# First_Board.net
KiCad netlist of a schematic drawn in EAGLE
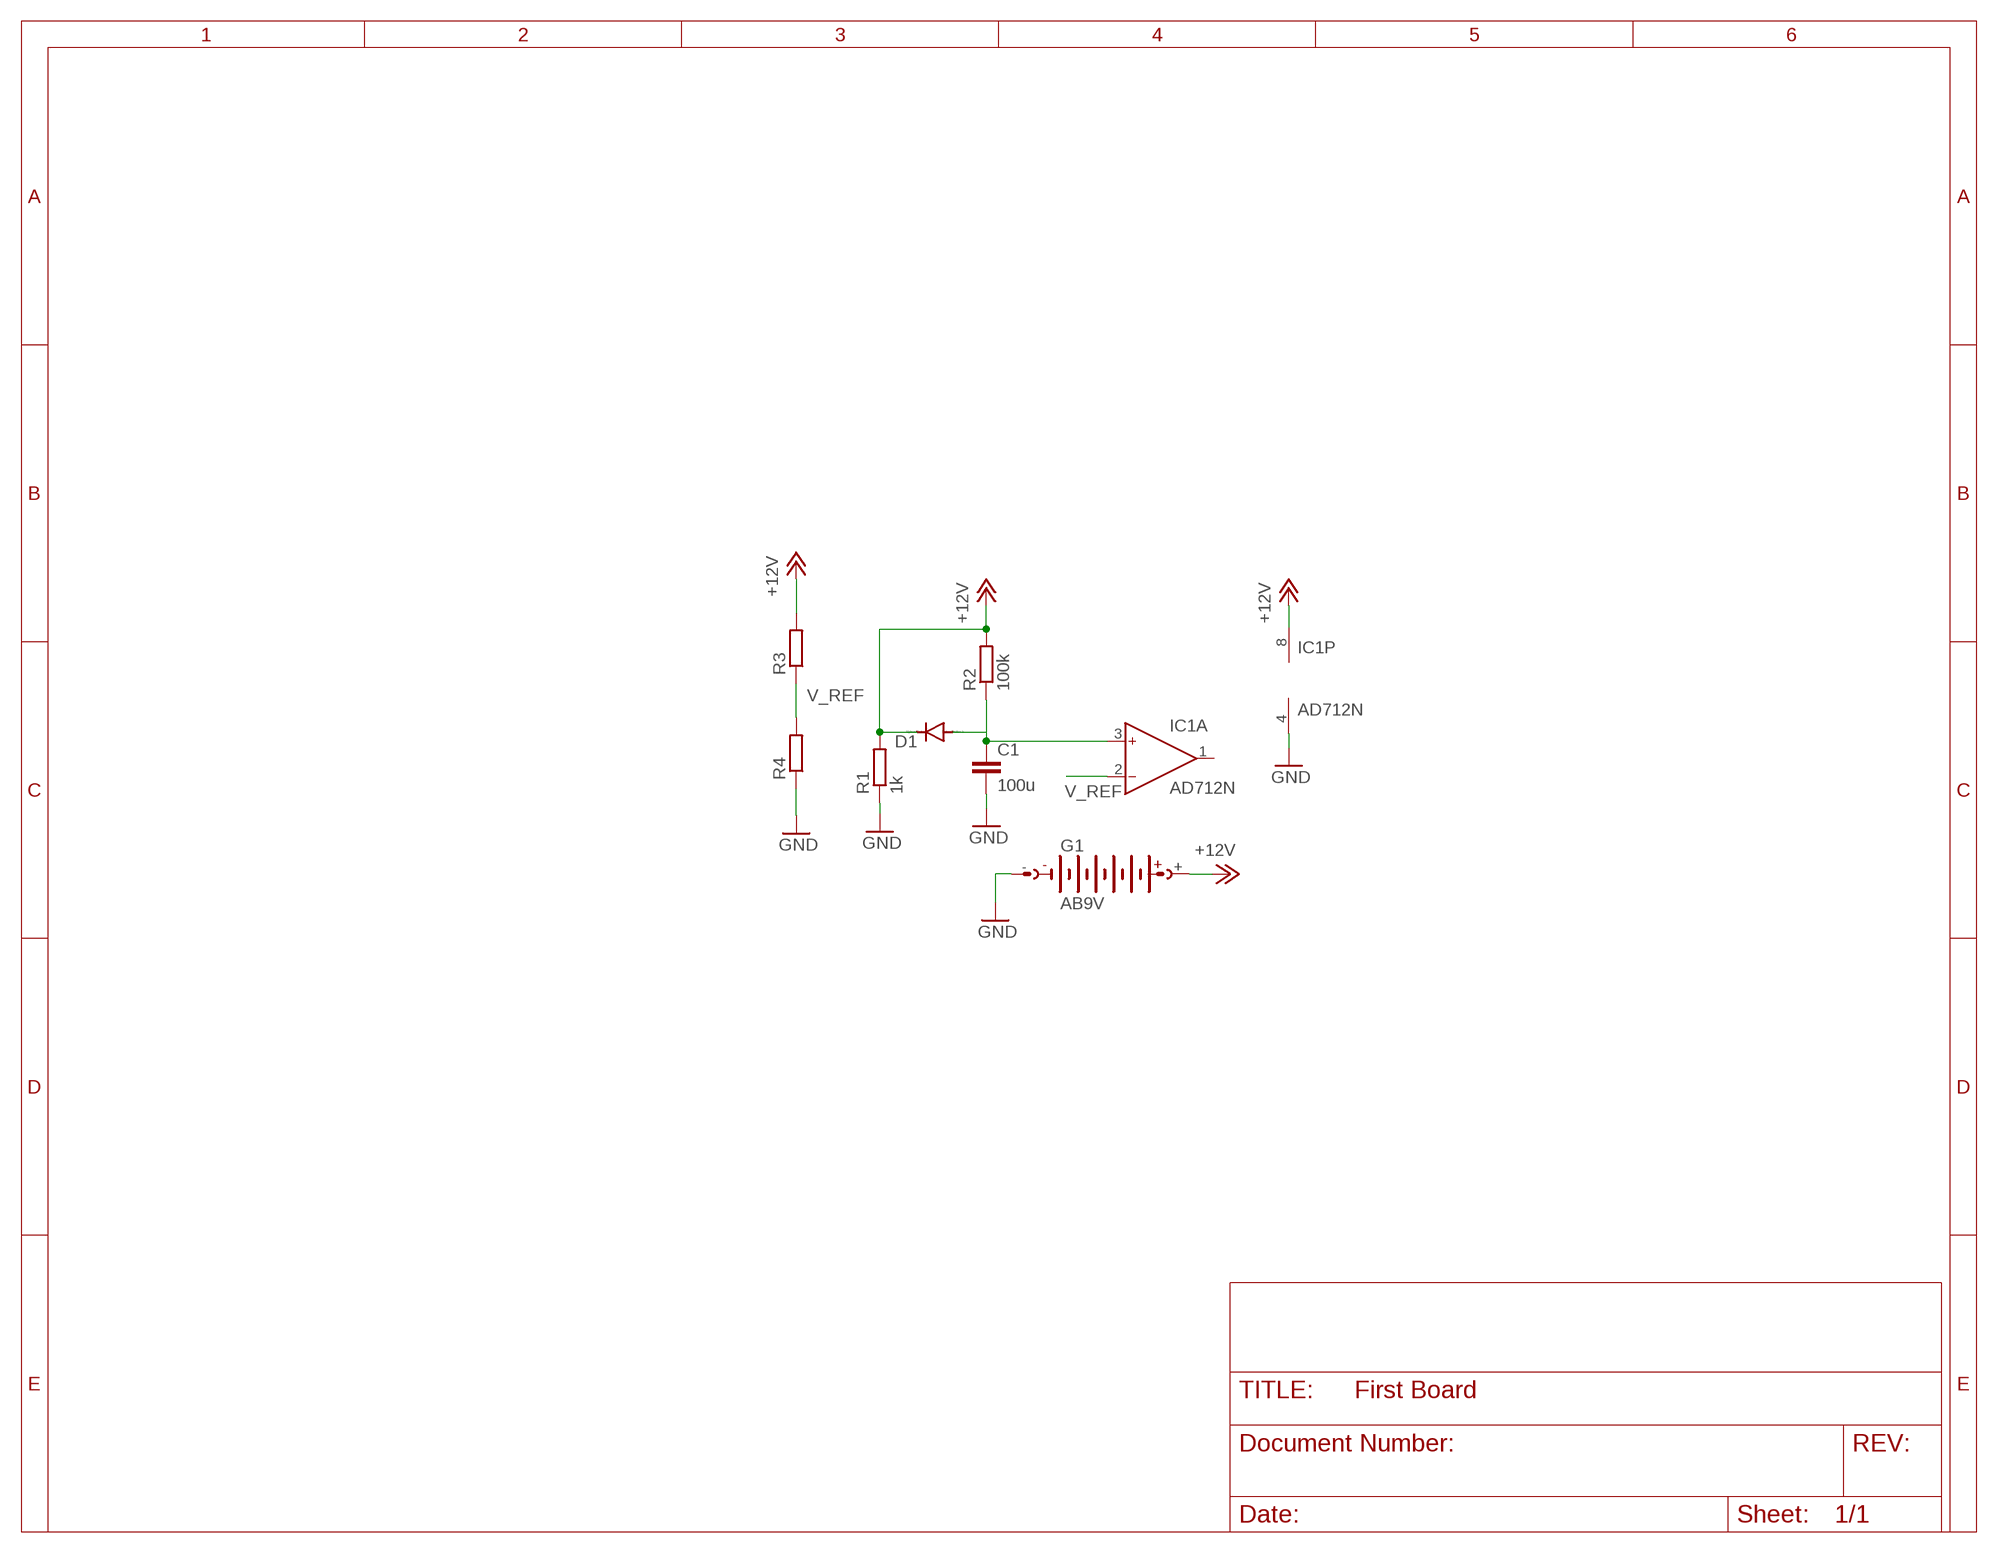
[diagram p0: schematic, sheet 1]

(export (version "E")
  (design (tool "Eeschema 10.0.6"))
  (components
    (comp (ref "C1")
      (value "100u")
      (footprint "eagle-import:C0805")
      (libsource (lib "eagle-import") (part "C-EUC0805"))
    )
    (comp (ref "D1")
      (value "DIODE-DO214AC")
      (footprint "eagle-import:DO214AC")
      (libsource (lib "eagle-import") (part "DIODE-DO214AC"))
    )
    (comp (ref "G1")
      (value "AB9V")
      (footprint "eagle-import:AB9V")
      (libsource (lib "eagle-import") (part "AB9V"))
    )
    (comp (ref "IC1")
      (value "AD712N")
      (footprint "eagle-import:DIL08")
      (fields (field (name "MF") "ALTERA CORPORATION") (field (name "MPN") "AD712JNZ"))
      (libsource (lib "eagle-import") (part "AD712N"))
    )
    (comp (ref "R1")
      (value "1k")
      (footprint "eagle-import:M0805")
      (libsource (lib "eagle-import") (part "R-EU_M0805"))
    )
    (comp (ref "R2")
      (value "100k")
      (footprint "eagle-import:M0805")
      (libsource (lib "eagle-import") (part "R-EU_M0805"))
    )
    (comp (ref "R3")
      (value "R-EU_M0805")
      (footprint "eagle-import:M0805")
      (libsource (lib "eagle-import") (part "R-EU_M0805"))
    )
    (comp (ref "R4")
      (value "R-EU_M0805")
      (footprint "eagle-import:M0805")
      (libsource (lib "eagle-import") (part "R-EU_M0805"))
    )
  )
  (nets
    (net (code "1") (name "+12V") (class "Default")
      (node (ref "D1") (pin "C") (pinfunction "C_C") (pintype "passive"))
      (node (ref "G1") (pin "+") (pinfunction "+_+") (pintype "passive"))
      (node (ref "IC1") (pin "8") (pinfunction "V+_8") (pintype "power_in"))
      (node (ref "R1") (pin "2") (pinfunction "2_2") (pintype "passive"))
      (node (ref "R2") (pin "2") (pinfunction "2_2") (pintype "passive"))
      (node (ref "R3") (pin "2") (pinfunction "2_2") (pintype "passive"))
    )
    (net (code "2") (name "/V_REF") (class "Default")
      (node (ref "IC1") (pin "2") (pinfunction "IN-_2") (pintype "input"))
      (node (ref "R3") (pin "1") (pinfunction "1_1") (pintype "passive"))
      (node (ref "R4") (pin "2") (pinfunction "2_2") (pintype "passive"))
    )
    (net (code "3") (name "GND") (class "Default")
      (node (ref "C1") (pin "2") (pinfunction "2_2") (pintype "passive"))
      (node (ref "G1") (pin "-") (pinfunction "-_-") (pintype "passive"))
      (node (ref "IC1") (pin "4") (pinfunction "V-_4") (pintype "power_in"))
      (node (ref "R1") (pin "1") (pinfunction "1_1") (pintype "passive"))
      (node (ref "R4") (pin "1") (pinfunction "1_1") (pintype "passive"))
    )
    (net (code "4") (name "Net-(IC1A-IN+)") (class "Default")
      (node (ref "C1") (pin "1") (pinfunction "1_1") (pintype "passive"))
      (node (ref "D1") (pin "A") (pinfunction "A_A") (pintype "passive"))
      (node (ref "IC1") (pin "3") (pinfunction "IN+_3") (pintype "input"))
      (node (ref "R2") (pin "1") (pinfunction "1_1") (pintype "passive"))
    )
    (net (code "5") (name "unconnected-(IC1A-OUT-Pad1)") (class "Default")
      (node (ref "IC1") (pin "1") (pinfunction "OUT_1") (pintype "output"))
    )
  )
)
